# m365_led_source.net
KiCad netlist of a schematic drawn in EAGLE
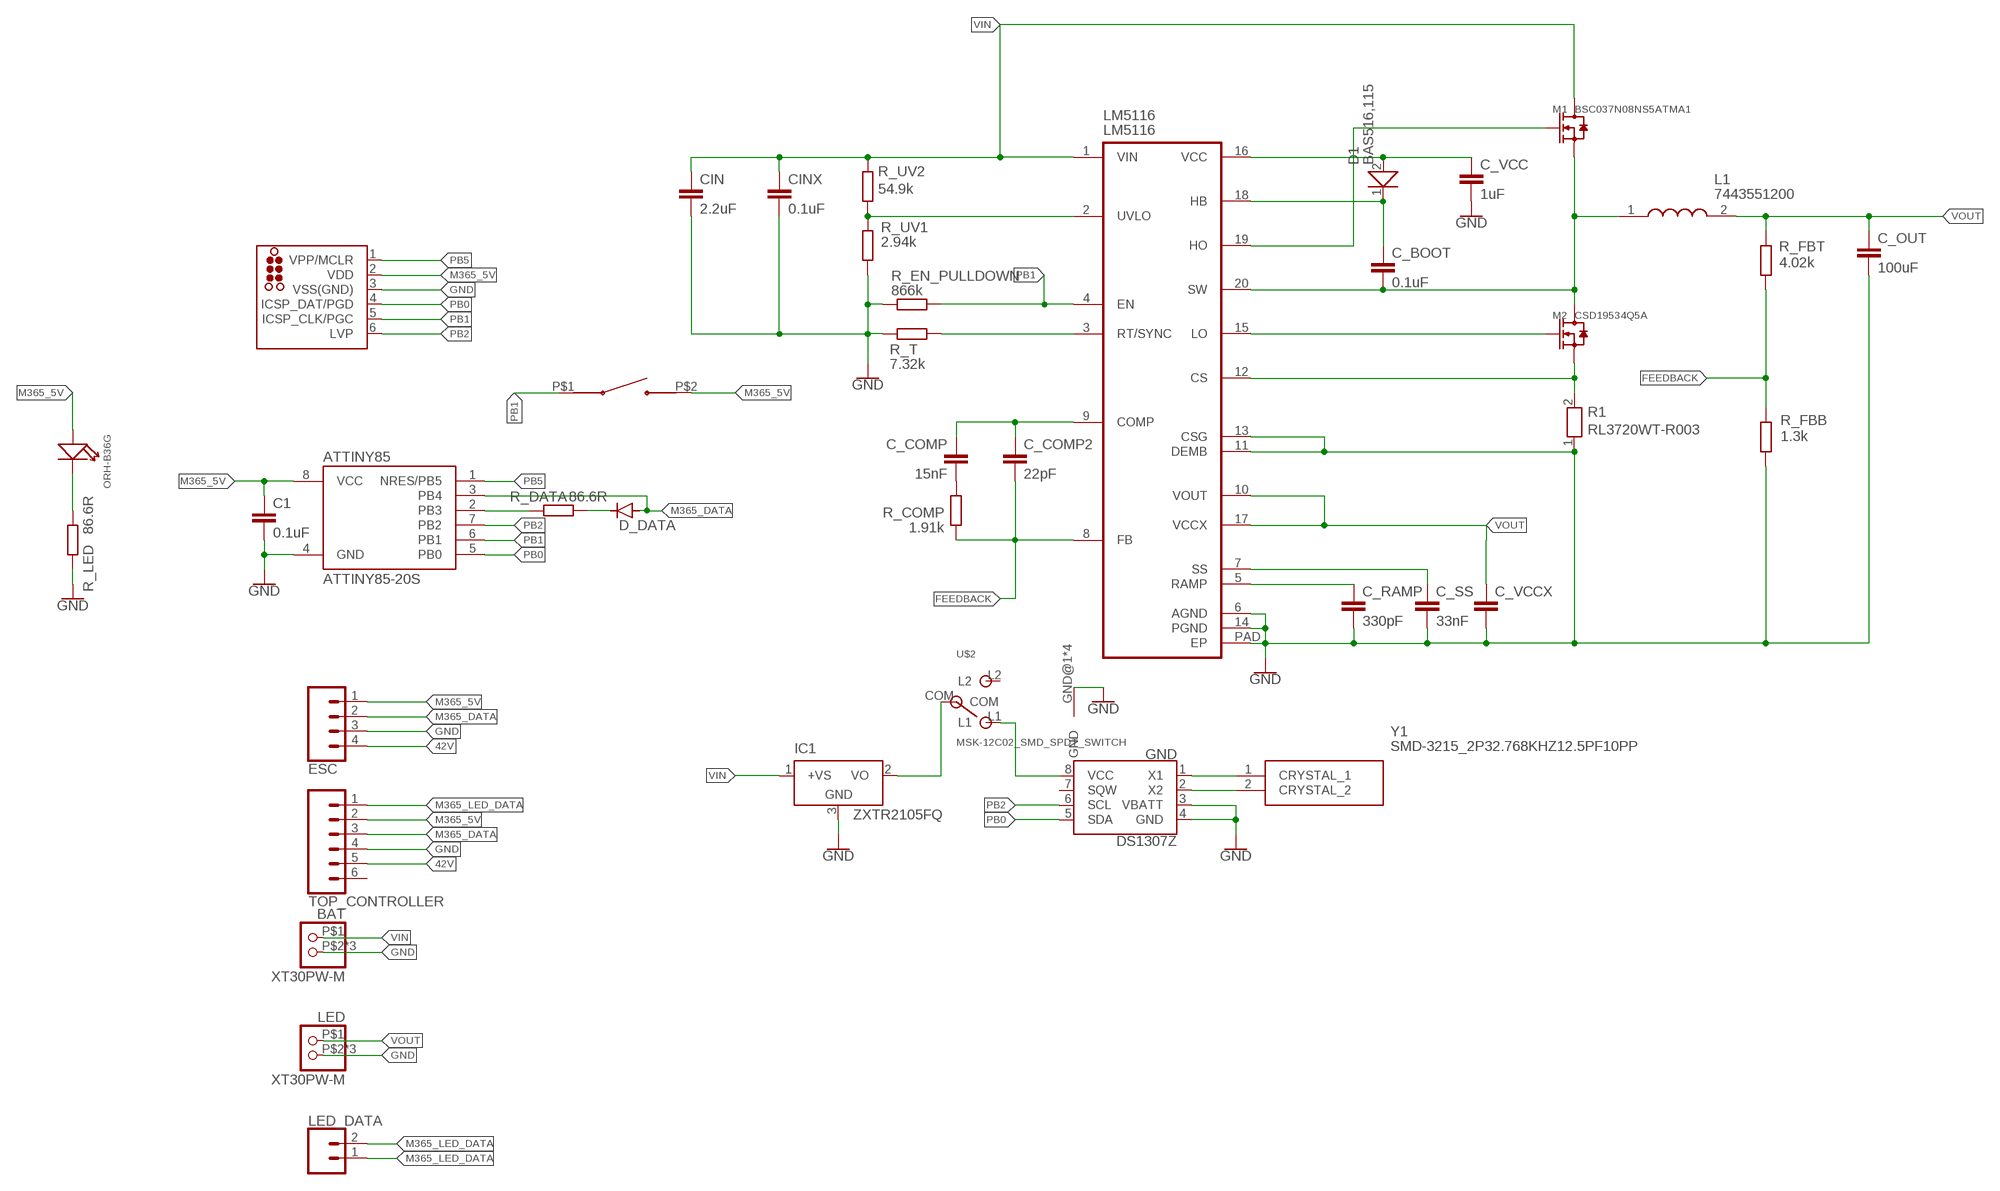
[diagram p0: schematic, sheet 1]

(export (version "E")
  (design (tool "Eeschema 10.0.6"))
  (components
    (comp (ref "ATTINY85")
      (value "ATTINY85-20S")
      (footprint "eagle-import:SOIC8_EIAJ_208MIL")
      (libsource (lib "eagle-import") (part "ATTINY85S-20"))
    )
    (comp (ref "BAT")
      (value "XT30PW-M")
      (footprint "eagle-import:XT30PW-M")
      (libsource (lib "eagle-import") (part "XT30PW-M"))
    )
    (comp (ref "C1")
      (value "0.1uF")
      (footprint "eagle-import:C0402")
      (libsource (lib "eagle-import") (part "CC0402"))
    )
    (comp (ref "CIN")
      (value "2.2uF")
      (footprint "eagle-import:C1210")
      (libsource (lib "eagle-import") (part "CC1210"))
    )
    (comp (ref "CINX")
      (value "0.1uF")
      (footprint "eagle-import:C0603")
      (libsource (lib "eagle-import") (part "CC0603"))
    )
    (comp (ref "C_BOOT")
      (value "0.1uF")
      (footprint "eagle-import:C0603")
      (libsource (lib "eagle-import") (part "CC0603"))
    )
    (comp (ref "C_COMP")
      (value "15nF")
      (footprint "eagle-import:C1005")
      (libsource (lib "eagle-import") (part "CC1005"))
    )
    (comp (ref "C_COMP2")
      (value "22pF")
      (footprint "eagle-import:C0402")
      (libsource (lib "eagle-import") (part "CC0402"))
    )
    (comp (ref "C_OUT")
      (value "100uF")
      (footprint "eagle-import:C1210")
      (libsource (lib "eagle-import") (part "CC1210"))
    )
    (comp (ref "C_RAMP")
      (value "330pF")
      (footprint "eagle-import:C0402")
      (libsource (lib "eagle-import") (part "CC0402"))
    )
    (comp (ref "C_SS")
      (value "33nF")
      (footprint "eagle-import:C0402")
      (libsource (lib "eagle-import") (part "CC0402"))
    )
    (comp (ref "C_VCC")
      (value "1uF")
      (footprint "eagle-import:C0402")
      (libsource (lib "eagle-import") (part "CC0402"))
    )
    (comp (ref "C_VCCX")
      (value "CC0402")
      (footprint "eagle-import:C0402")
      (libsource (lib "eagle-import") (part "CC0402"))
    )
    (comp (ref "D1")
      (value "BAS516,115")
      (footprint "eagle-import:SOD1608X65N")
      (fields (field (name "MOUSER_PART_NUMBER") "771-BAS516-T/R") (field (name "RS_PART_NUMBER") "0508282"))
      (libsource (lib "eagle-import") (part "BAS516,115"))
    )
    (comp (ref "D_DATA")
      (value "SMAFJ75A")
      (footprint "eagle-import:SMAFJ75A")
      (libsource (lib "eagle-import") (part "SMAFJ75A"))
    )
    (comp (ref "ESC")
      (value "CONN_04LONGPADS")
      (footprint "eagle-import:1X04_LONGPADS")
      (libsource (lib "eagle-import") (part "CONN_04LONGPADS"))
    )
    (comp (ref "GND")
      (value "DS1307Z")
      (footprint "eagle-import:SO08-0.15")
      (libsource (lib "eagle-import") (part "DS1307Z"))
    )
    (comp (ref "IC1")
      (value "ZXTR2105FQ")
      (footprint "eagle-import:SOT23")
      (libsource (lib "eagle-import") (part "LM50"))
    )
    (comp (ref "J2")
      (value "TC2030-MCP-NL")
      (footprint "eagle-import:TC2030-MCP-NL")
      (libsource (lib "eagle-import") (part "TC2030-MCP-NL"))
    )
    (comp (ref "L1")
      (value "7443551200")
      (footprint "eagle-import:WE-HCI_1350_136523")
      (fields (field (name "MOUSER_PART_NUMBER") "710-7443551200") (field (name "RS_PART_NUMBER") "7362049P"))
      (libsource (lib "eagle-import") (part "7443551200"))
    )
    (comp (ref "LED")
      (value "XT30PW-M")
      (footprint "eagle-import:XT30PW-M")
      (libsource (lib "eagle-import") (part "XT30PW-M"))
    )
    (comp (ref "LED_DATA")
      (value "CONN_02PTH3")
      (footprint "eagle-import:1X02_LONGPADS")
      (libsource (lib "eagle-import") (part "CONN_02PTH3"))
    )
    (comp (ref "LM5116")
      (value "LM5116")
      (footprint "eagle-import:TSSOP20-PAD")
      (libsource (lib "eagle-import") (part "LM5116"))
    )
    (comp (ref "M1")
      (value "BSC037N08NS5ATMA1")
      (footprint "eagle-import:CSD19531Q5AT")
      (fields
        (field (name "MANUFACTURER_PART_NUMBER") "CSD19534Q5A")
        (field (name "MOUSER_PART_NUMBER") "595-CSD19534Q5A")
      )
      (libsource (lib "eagle-import") (part "CSD19534Q5A"))
    )
    (comp (ref "M2")
      (value "CSD19534Q5A")
      (footprint "eagle-import:CSD19531Q5AT")
      (fields (field (name "MOUSER_PART_NUMBER") "595-CSD19534Q5A"))
      (libsource (lib "eagle-import") (part "CSD19534Q5A"))
    )
    (comp (ref "R1")
      (value "RL3720WT-R003")
      (footprint "eagle-import:RESC2038X70N")
      (fields
        (field (name "MANUFACTURER_PART_NUMBER") "RL3720WT-R005-F")
        (field (name "MOUSER_PART_NUMBER") "754-RL3720WT-R005-F")
      )
      (libsource (lib "eagle-import") (part "RL3720WT-R005-F"))
    )
    (comp (ref "R_COMP")
      (value "1.91k")
      (footprint "eagle-import:R0402")
      (libsource (lib "eagle-import") (part "RR0402"))
    )
    (comp (ref "R_DATA")
      (value "86.6R")
      (footprint "eagle-import:R0402")
      (libsource (lib "eagle-import") (part "RR0402"))
    )
    (comp (ref "R_EN_PULLDOWN")
      (value "866k")
      (footprint "eagle-import:R0402")
      (libsource (lib "eagle-import") (part "RR0402"))
    )
    (comp (ref "R_FBB")
      (value "1.3k")
      (footprint "eagle-import:R1206")
      (libsource (lib "eagle-import") (part "RR1206"))
    )
    (comp (ref "R_FBT")
      (value "4.02k")
      (footprint "eagle-import:R1206")
      (libsource (lib "eagle-import") (part "RR1206"))
    )
    (comp (ref "R_LED")
      (value "86.6R")
      (footprint "eagle-import:R0402")
      (libsource (lib "eagle-import") (part "RR0402"))
    )
    (comp (ref "R_T")
      (value "7.32k")
      (footprint "eagle-import:R0402")
      (libsource (lib "eagle-import") (part "RR0402"))
    )
    (comp (ref "R_UV1")
      (value "2.94k")
      (footprint "eagle-import:R0402")
      (libsource (lib "eagle-import") (part "RR0402"))
    )
    (comp (ref "R_UV2")
      (value "54.9k")
      (footprint "eagle-import:R0402")
      (libsource (lib "eagle-import") (part "RR0402"))
    )
    (comp (ref "TINY_LED")
      (value "ORH-B36G")
      (footprint "eagle-import:LED-0603")
      (fields (field (name "MPN") "19-217-BHC-ZL1M2RY-3T"))
      (libsource (lib "eagle-import") (part "SMD-LED-CLEAR-BLUE(0603)"))
    )
    (comp (ref "TOP_CONTROLLER")
      (value "CONN_06LONGPADS")
      (footprint "eagle-import:1X06_LONGPADS")
      (libsource (lib "eagle-import") (part "CONN_06LONGPADS"))
    )
    (comp (ref "U$1")
      (value "TL3302BF260QJ")
      (footprint "eagle-import:TL3302BF260QJ")
      (libsource (lib "eagle-import") (part "TL3302BF260QJ"))
    )
    (comp (ref "U$2")
      (value "MSK-12C02_SMD_SPDT_SWITCH")
      (footprint "eagle-import:MSK-12C02")
      (libsource (lib "eagle-import") (part "MSK-12C02_SMD_SPDT_SWITCH"))
    )
    (comp (ref "Y1")
      (value "SMD-3215_2P32.768KHZ12.5PF10PP")
      (footprint "eagle-import:SMD3215_2P32768KHZ125PF10PPM")
      (fields (field (name "MANUFACTURER_PART_NUMBER") "SMD-3215_2P32.768KHZ12.5PF10PPM"))
      (libsource (lib "eagle-import") (part "SMD-3215_2P32.768KHZ12.5PF10PP"))
    )
  )
  (nets
    (net (code "1") (name "42V") (class "Default")
      (node (ref "ESC") (pin "4") (pinfunction "4_4") (pintype "passive"))
      (node (ref "TOP_CONTROLLER") (pin "5") (pinfunction "5_5") (pintype "passive"))
    )
    (net (code "2") (name "FEEDBACK") (class "Default")
      (node (ref "C_COMP2") (pin "2") (pinfunction "2_2") (pintype "passive"))
      (node (ref "LM5116") (pin "8") (pinfunction "FB_8") (pintype "input"))
      (node (ref "R_COMP") (pin "1") (pinfunction "1_1") (pintype "passive"))
      (node (ref "R_FBB") (pin "2") (pinfunction "2_2") (pintype "passive"))
      (node (ref "R_FBT") (pin "1") (pinfunction "1_1") (pintype "passive"))
    )
    (net (code "3") (name "GND") (class "Default")
      (node (ref "ATTINY85") (pin "4") (pinfunction "GND_4") (pintype "power_in"))
      (node (ref "BAT") (pin "P$2") (pinfunction "2_P$2") (pintype "passive"))
      (node (ref "BAT") (pin "P$3") (pinfunction "2_P$3") (pintype "passive"))
      (node (ref "BAT") (pin "P$4") (pinfunction "2_P$4") (pintype "passive"))
      (node (ref "C1") (pin "2") (pinfunction "2_2") (pintype "passive"))
      (node (ref "CIN") (pin "2") (pinfunction "2_2") (pintype "passive"))
      (node (ref "CINX") (pin "2") (pinfunction "2_2") (pintype "passive"))
      (node (ref "C_OUT") (pin "2") (pinfunction "2_2") (pintype "passive"))
      (node (ref "C_RAMP") (pin "2") (pinfunction "2_2") (pintype "passive"))
      (node (ref "C_SS") (pin "2") (pinfunction "2_2") (pintype "passive"))
      (node (ref "C_VCC") (pin "2") (pinfunction "2_2") (pintype "passive"))
      (node (ref "C_VCCX") (pin "2") (pinfunction "2_2") (pintype "passive"))
      (node (ref "ESC") (pin "3") (pinfunction "3_3") (pintype "passive"))
      (node (ref "GND") (pin "3") (pinfunction "VBATT_3") (pintype "bidirectional"))
      (node (ref "GND") (pin "4") (pinfunction "GND_4") (pintype "bidirectional"))
      (node (ref "IC1") (pin "3") (pinfunction "GND_3") (pintype "power_in"))
      (node (ref "J2") (pin "3") (pinfunction "VSS(GND)_3") (pintype "power_in"))
      (node (ref "LED") (pin "P$2") (pinfunction "2_P$2") (pintype "passive"))
      (node (ref "LED") (pin "P$3") (pinfunction "2_P$3") (pintype "passive"))
      (node (ref "LED") (pin "P$4") (pinfunction "2_P$4") (pintype "passive"))
      (node (ref "LM5116") (pin "11") (pinfunction "DEMB_11") (pintype "input"))
      (node (ref "LM5116") (pin "13") (pinfunction "CSG_13") (pintype "input"))
      (node (ref "LM5116") (pin "14") (pinfunction "PGND_14") (pintype "power_in"))
      (node (ref "LM5116") (pin "6") (pinfunction "AGND_6") (pintype "passive"))
      (node (ref "LM5116") (pin "PAD") (pinfunction "EP_PAD") (pintype "power_in"))
      (node (ref "R1") (pin "1") (pinfunction "1_1") (pintype "bidirectional"))
      (node (ref "R_EN_PULLDOWN") (pin "1") (pinfunction "1_1") (pintype "passive"))
      (node (ref "R_FBB") (pin "1") (pinfunction "1_1") (pintype "passive"))
      (node (ref "R_LED") (pin "1") (pinfunction "1_1") (pintype "passive"))
      (node (ref "R_T") (pin "1") (pinfunction "1_1") (pintype "passive"))
      (node (ref "R_UV1") (pin "1") (pinfunction "1_1") (pintype "passive"))
      (node (ref "TOP_CONTROLLER") (pin "4") (pinfunction "4_4") (pintype "passive"))
      (node (ref "U$2") (pin "GND@1") (pinfunction "GND_GND@1") (pintype "bidirectional"))
      (node (ref "U$2") (pin "GND@2") (pinfunction "GND_GND@2") (pintype "bidirectional"))
      (node (ref "U$2") (pin "GND@3") (pinfunction "GND_GND@3") (pintype "bidirectional"))
      (node (ref "U$2") (pin "GND@4") (pinfunction "GND_GND@4") (pintype "bidirectional"))
    )
    (net (code "4") (name "M365_5V") (class "Default")
      (node (ref "ATTINY85") (pin "8") (pinfunction "VCC_8") (pintype "power_in"))
      (node (ref "C1") (pin "1") (pinfunction "1_1") (pintype "passive"))
      (node (ref "ESC") (pin "1") (pinfunction "1_1") (pintype "passive"))
      (node (ref "J2") (pin "2") (pinfunction "VDD_2") (pintype "power_in"))
      (node (ref "TINY_LED") (pin "+") (pinfunction "+_+") (pintype "passive"))
      (node (ref "TOP_CONTROLLER") (pin "2") (pinfunction "2_2") (pintype "passive"))
      (node (ref "U$1") (pin "P$2") (pinfunction "P$2_P$2") (pintype "bidirectional"))
    )
    (net (code "5") (name "M365_DATA") (class "Default")
      (node (ref "ATTINY85") (pin "3") (pinfunction "PB4_3") (pintype "bidirectional"))
      (node (ref "D_DATA") (pin "P$2") (pinfunction "ANODE_P$2") (pintype "bidirectional"))
      (node (ref "ESC") (pin "2") (pinfunction "2_2") (pintype "passive"))
      (node (ref "TOP_CONTROLLER") (pin "3") (pinfunction "3_3") (pintype "passive"))
    )
    (net (code "6") (name "M365_LED_DATA") (class "Default")
      (node (ref "LED_DATA") (pin "1") (pinfunction "1_1") (pintype "passive"))
      (node (ref "LED_DATA") (pin "2") (pinfunction "2_2") (pintype "passive"))
      (node (ref "TOP_CONTROLLER") (pin "1") (pinfunction "1_1") (pintype "passive"))
    )
    (net (code "7") (name "Net-(ATTINY85-PB3)") (class "Default")
      (node (ref "ATTINY85") (pin "2") (pinfunction "PB3_2") (pintype "bidirectional"))
      (node (ref "R_DATA") (pin "1") (pinfunction "1_1") (pintype "passive"))
    )
    (net (code "8") (name "Net-(C_COMP-Pad2)") (class "Default")
      (node (ref "C_COMP") (pin "2") (pinfunction "2_2") (pintype "passive"))
      (node (ref "R_COMP") (pin "2") (pinfunction "2_2") (pintype "passive"))
    )
    (net (code "9") (name "Net-(D_DATA-CATHODE)") (class "Default")
      (node (ref "D_DATA") (pin "P$1") (pinfunction "CATHODE_P$1") (pintype "bidirectional"))
      (node (ref "R_DATA") (pin "2") (pinfunction "2_2") (pintype "passive"))
    )
    (net (code "10") (name "Net-(GND-VCC)") (class "Default")
      (node (ref "GND") (pin "8") (pinfunction "VCC_8") (pintype "bidirectional"))
      (node (ref "U$2") (pin "L1") (pinfunction "L1_L1") (pintype "bidirectional"))
    )
    (net (code "11") (name "Net-(GND-X1)") (class "Default")
      (node (ref "GND") (pin "1") (pinfunction "X1_1") (pintype "bidirectional"))
      (node (ref "Y1") (pin "1") (pinfunction "CRYSTAL_1_1") (pintype "bidirectional"))
    )
    (net (code "12") (name "Net-(GND-X2)") (class "Default")
      (node (ref "GND") (pin "2") (pinfunction "X2_2") (pintype "bidirectional"))
      (node (ref "Y1") (pin "2") (pinfunction "CRYSTAL_2_2") (pintype "bidirectional"))
    )
    (net (code "13") (name "Net-(IC1-VO)") (class "Default")
      (node (ref "IC1") (pin "2") (pinfunction "VO_2") (pintype "input"))
      (node (ref "U$2") (pin "COM") (pinfunction "COM_COM") (pintype "bidirectional"))
    )
    (net (code "14") (name "Net-(LM5116-COMP)") (class "Default")
      (node (ref "C_COMP") (pin "1") (pinfunction "1_1") (pintype "passive"))
      (node (ref "C_COMP2") (pin "1") (pinfunction "1_1") (pintype "passive"))
      (node (ref "LM5116") (pin "9") (pinfunction "COMP_9") (pintype "output"))
    )
    (net (code "15") (name "Net-(LM5116-CS)") (class "Default")
      (node (ref "LM5116") (pin "12") (pinfunction "CS_12") (pintype "input"))
      (node (ref "M2") (pin "1") (pinfunction "S_1") (pintype "passive"))
      (node (ref "M2") (pin "2") (pinfunction "S_2") (pintype "passive"))
      (node (ref "M2") (pin "3") (pinfunction "S_3") (pintype "passive"))
      (node (ref "R1") (pin "2") (pinfunction "2_2") (pintype "bidirectional"))
    )
    (net (code "16") (name "Net-(LM5116-HB)") (class "Default")
      (node (ref "C_BOOT") (pin "1") (pinfunction "1_1") (pintype "passive"))
      (node (ref "D1") (pin "1") (pinfunction "1_1") (pintype "bidirectional"))
      (node (ref "LM5116") (pin "18") (pinfunction "HB_18") (pintype "passive"))
    )
    (net (code "17") (name "Net-(LM5116-HO)") (class "Default")
      (node (ref "LM5116") (pin "19") (pinfunction "HO_19") (pintype "output"))
      (node (ref "M1") (pin "4") (pinfunction "G_4") (pintype "passive"))
    )
    (net (code "18") (name "Net-(LM5116-LO)") (class "Default")
      (node (ref "LM5116") (pin "15") (pinfunction "LO_15") (pintype "output"))
      (node (ref "M2") (pin "4") (pinfunction "G_4") (pintype "passive"))
    )
    (net (code "19") (name "Net-(LM5116-RAMP)") (class "Default")
      (node (ref "C_RAMP") (pin "1") (pinfunction "1_1") (pintype "passive"))
      (node (ref "LM5116") (pin "5") (pinfunction "RAMP_5") (pintype "passive"))
    )
    (net (code "20") (name "Net-(LM5116-RT{slash}SYNC)") (class "Default")
      (node (ref "LM5116") (pin "3") (pinfunction "RT/SYNC_3") (pintype "passive"))
      (node (ref "R_T") (pin "2") (pinfunction "2_2") (pintype "passive"))
    )
    (net (code "21") (name "Net-(LM5116-SS)") (class "Default")
      (node (ref "C_SS") (pin "1") (pinfunction "1_1") (pintype "passive"))
      (node (ref "LM5116") (pin "7") (pinfunction "SS_7") (pintype "passive"))
    )
    (net (code "22") (name "Net-(LM5116-SW)") (class "Default")
      (node (ref "C_BOOT") (pin "2") (pinfunction "2_2") (pintype "passive"))
      (node (ref "L1") (pin "1") (pinfunction "1_1") (pintype "bidirectional"))
      (node (ref "LM5116") (pin "20") (pinfunction "SW_20") (pintype "passive"))
      (node (ref "M1") (pin "1") (pinfunction "S_1") (pintype "passive"))
      (node (ref "M1") (pin "2") (pinfunction "S_2") (pintype "passive"))
      (node (ref "M1") (pin "3") (pinfunction "S_3") (pintype "passive"))
      (node (ref "M2") (pin "5") (pinfunction "D_5") (pintype "passive"))
      (node (ref "M2") (pin "6") (pinfunction "D_6") (pintype "passive"))
      (node (ref "M2") (pin "7") (pinfunction "D_7") (pintype "passive"))
      (node (ref "M2") (pin "8") (pinfunction "D_8") (pintype "passive"))
      (node (ref "M2") (pin "9") (pinfunction "D_9") (pintype "passive"))
    )
    (net (code "23") (name "Net-(LM5116-UVLO)") (class "Default")
      (node (ref "LM5116") (pin "2") (pinfunction "UVLO_2") (pintype "passive"))
      (node (ref "R_UV1") (pin "2") (pinfunction "2_2") (pintype "passive"))
      (node (ref "R_UV2") (pin "1") (pinfunction "1_1") (pintype "passive"))
    )
    (net (code "24") (name "Net-(LM5116-VCC)") (class "Default")
      (node (ref "C_VCC") (pin "1") (pinfunction "1_1") (pintype "passive"))
      (node (ref "D1") (pin "2") (pinfunction "2_2") (pintype "bidirectional"))
      (node (ref "LM5116") (pin "16") (pinfunction "VCC_16") (pintype "power_in"))
    )
    (net (code "25") (name "Net-(R_LED-Pad2)") (class "Default")
      (node (ref "R_LED") (pin "2") (pinfunction "2_2") (pintype "passive"))
      (node (ref "TINY_LED") (pin "-") (pinfunction "-_-") (pintype "passive"))
    )
    (net (code "26") (name "PB0") (class "Default")
      (node (ref "ATTINY85") (pin "5") (pinfunction "PB0_5") (pintype "bidirectional"))
      (node (ref "GND") (pin "5") (pinfunction "SDA_5") (pintype "bidirectional"))
      (node (ref "J2") (pin "4") (pinfunction "ICSP_DAT/PGD_4") (pintype "bidirectional"))
    )
    (net (code "27") (name "PB1") (class "Default")
      (node (ref "ATTINY85") (pin "6") (pinfunction "PB1_6") (pintype "bidirectional"))
      (node (ref "J2") (pin "5") (pinfunction "ICSP_CLK/PGC_5") (pintype "output"))
      (node (ref "LM5116") (pin "4") (pinfunction "EN_4") (pintype "input"))
      (node (ref "R_EN_PULLDOWN") (pin "2") (pinfunction "2_2") (pintype "passive"))
      (node (ref "U$1") (pin "P$1") (pinfunction "P$1_P$1") (pintype "bidirectional"))
    )
    (net (code "28") (name "PB2") (class "Default")
      (node (ref "ATTINY85") (pin "7") (pinfunction "PB2_7") (pintype "bidirectional"))
      (node (ref "GND") (pin "6") (pinfunction "SCL_6") (pintype "bidirectional"))
      (node (ref "J2") (pin "6") (pinfunction "LVP_6") (pintype "bidirectional"))
    )
    (net (code "29") (name "PB5") (class "Default")
      (node (ref "ATTINY85") (pin "1") (pinfunction "NRES/PB5_1") (pintype "bidirectional"))
      (node (ref "J2") (pin "1") (pinfunction "VPP/MCLR_1") (pintype "passive"))
    )
    (net (code "30") (name "VIN") (class "Default")
      (node (ref "BAT") (pin "P$1") (pinfunction "1_P$1") (pintype "passive"))
      (node (ref "CIN") (pin "1") (pinfunction "1_1") (pintype "passive"))
      (node (ref "CINX") (pin "1") (pinfunction "1_1") (pintype "passive"))
      (node (ref "IC1") (pin "1") (pinfunction "+VS_1") (pintype "input"))
      (node (ref "LM5116") (pin "1") (pinfunction "VIN_1") (pintype "power_in"))
      (node (ref "M1") (pin "5") (pinfunction "D_5") (pintype "passive"))
      (node (ref "M1") (pin "6") (pinfunction "D_6") (pintype "passive"))
      (node (ref "M1") (pin "7") (pinfunction "D_7") (pintype "passive"))
      (node (ref "M1") (pin "8") (pinfunction "D_8") (pintype "passive"))
      (node (ref "M1") (pin "9") (pinfunction "D_9") (pintype "passive"))
      (node (ref "R_UV2") (pin "2") (pinfunction "2_2") (pintype "passive"))
    )
    (net (code "31") (name "VOUT") (class "Default")
      (node (ref "C_OUT") (pin "1") (pinfunction "1_1") (pintype "passive"))
      (node (ref "C_VCCX") (pin "1") (pinfunction "1_1") (pintype "passive"))
      (node (ref "L1") (pin "2") (pinfunction "2_2") (pintype "bidirectional"))
      (node (ref "LED") (pin "P$1") (pinfunction "1_P$1") (pintype "passive"))
      (node (ref "LM5116") (pin "10") (pinfunction "VOUT_10") (pintype "input"))
      (node (ref "LM5116") (pin "17") (pinfunction "VCCX_17") (pintype "power_in"))
      (node (ref "R_FBT") (pin "2") (pinfunction "2_2") (pintype "passive"))
    )
    (net (code "32") (name "unconnected-(GND-SQW-Pad7)") (class "Default")
      (node (ref "GND") (pin "7") (pinfunction "SQW_7") (pintype "bidirectional"))
    )
    (net (code "33") (name "unconnected-(TOP_CONTROLLER-Pad6)") (class "Default")
      (node (ref "TOP_CONTROLLER") (pin "6") (pinfunction "6_6") (pintype "passive"))
    )
    (net (code "34") (name "unconnected-(U$2-PadL2)") (class "Default")
      (node (ref "U$2") (pin "L2") (pinfunction "L2_L2") (pintype "bidirectional"))
    )
  )
)
